# USB2UART.net
KiCad netlist of a schematic drawn in Altium Designer
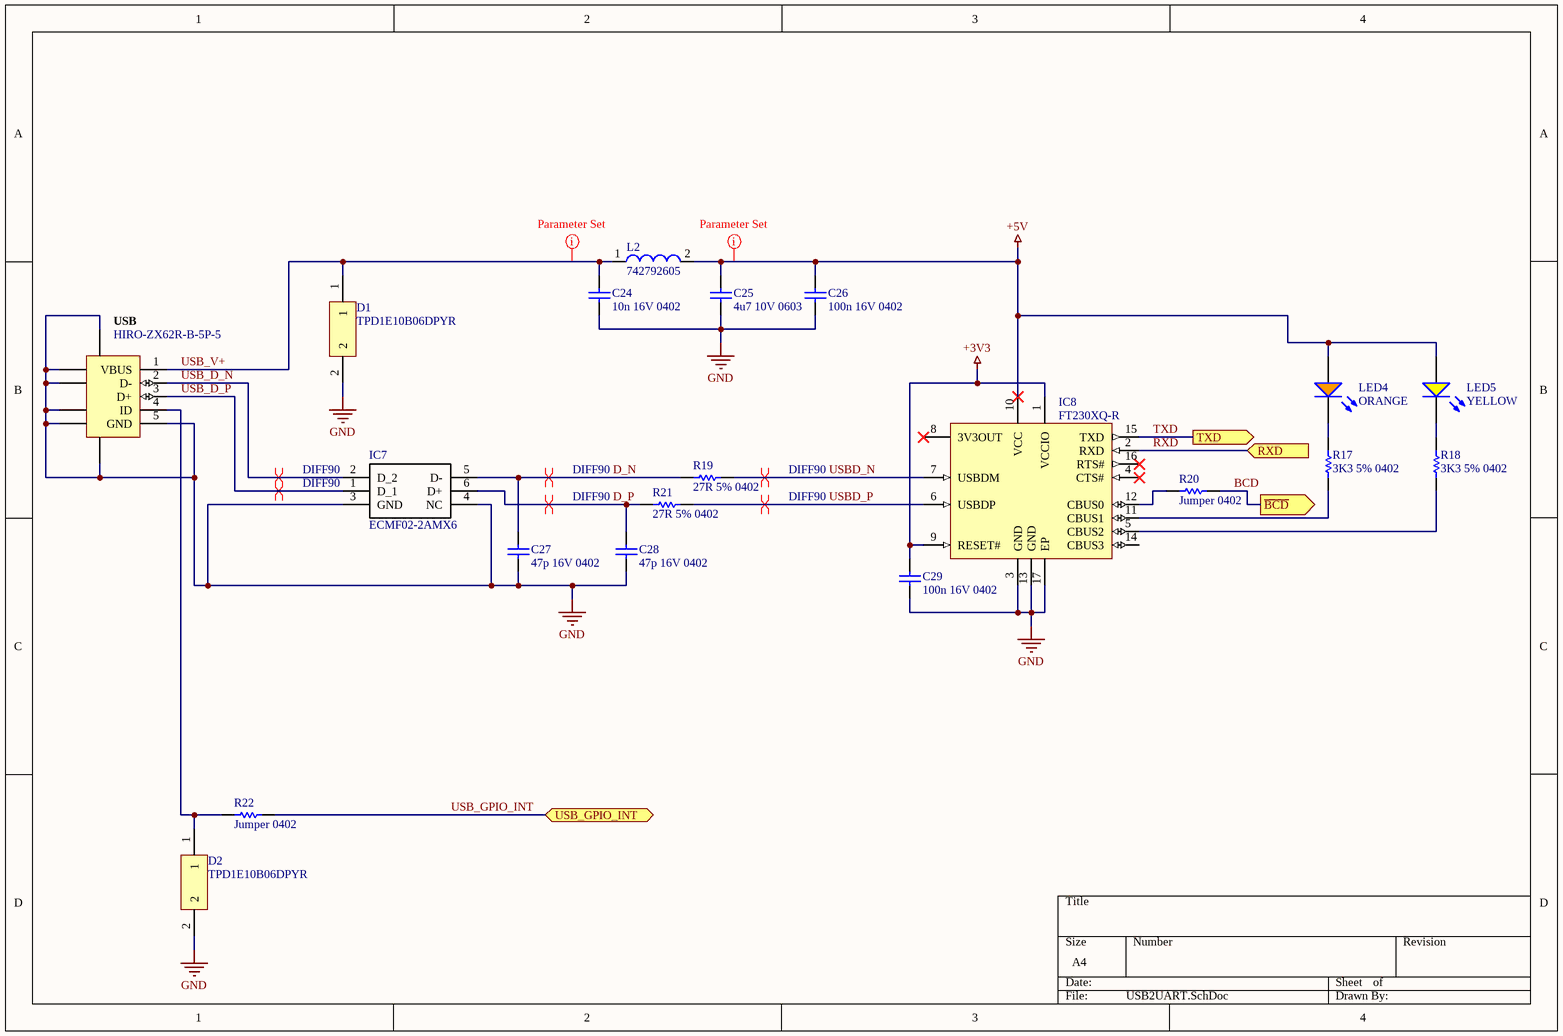
[diagram p0: USB2UART.SchDoc]

(export (version "E")
  (design (tool "Eeschema 10.0.6"))
  (components
    (comp (ref "C24")
      (value "10n 16V 0402")
      (footprint "CAPC0402(1005)33_L")
      (description "CAP 10nF 16V ±10% 0402 (1005 Metric) Thickness 0.33mm SMD")
      (fields (field (name "TOLERANCE") "Â±10%"))
      (libsource (lib "Altium Content Vault") (part "CAP"))
    )
    (comp (ref "C25")
      (value "4u7 10V 0603")
      (footprint "CAPC0603(1608)100_L")
      (description "CAP 4.7uF 10V ±20% 0603 (1608 Metric) Thickness 1mm SMD")
      (fields (field (name "TOLERANCE") "Â±20%"))
      (libsource (lib "Altium Content Vault") (part "CAP"))
    )
    (comp (ref "C26")
      (value "100n 16V 0402")
      (footprint "CAPC0402(1005)60_L")
      (description "CAP 100nF 16V ±10% 0402 (1005 Metric) Thickness 0.6mm SMD")
      (fields (field (name "TOLERANCE") "Â±10%"))
      (libsource (lib "Altium Content Vault") (part "CAP"))
    )
    (comp (ref "C27")
      (value "47p 16V 0402")
      (footprint "CAPC0402(1005)60_L")
      (description "CAP 47pF 16V ±10% 0402 (1005 Metric) Thickness 0.6mm SMD")
      (fields (field (name "TOLERANCE") "Â±10%"))
      (libsource (lib "Altium Content Vault") (part "CAP"))
    )
    (comp (ref "C28")
      (value "47p 16V 0402")
      (footprint "CAPC0402(1005)60_L")
      (description "CAP 47pF 16V ±10% 0402 (1005 Metric) Thickness 0.6mm SMD")
      (fields (field (name "TOLERANCE") "Â±10%"))
      (libsource (lib "Altium Content Vault") (part "CAP"))
    )
    (comp (ref "C29")
      (value "100n 16V 0402")
      (footprint "CAPC0402(1005)60_N")
      (description "CAP 100nF 16V ±10% 0402 (1005 Metric) Thickness 0.6mm SMD")
      (fields (field (name "TOLERANCE") "Â±10%"))
      (libsource (lib "Altium Content Vault") (part "CAP"))
    )
    (comp (ref "D1")
      (value "TPD1E10B06DPYR")
      (footprint "DPY0002A_M")
      (fields (field (name "MANUFACTURER") "Texas Instruments"))
      (libsource (lib "Altium Content Vault") (part "TI-TPD1E10B06-X2SON_DPY-2"))
    )
    (comp (ref "D2")
      (value "TPD1E10B06DPYR")
      (footprint "DPY0002A_M")
      (fields (field (name "MANUFACTURER") "Texas Instruments"))
      (libsource (lib "Altium Content Vault") (part "TI-TPD1E10B06-X2SON_DPY-2"))
    )
    (comp (ref "IC7")
      (value "ECMF02-2AMX6")
      (footprint "SON50P150X170X55-6N-D")
      (description "Integrated Circuit")
      (fields
        (field (name "MOUSER PART NUMBER") "511-ECMF02-2AMX6")
        (field (name "RS PART NUMBER") "8805276")
      )
      (libsource (lib "bleimuv6_intlib") (part "ECMF02-2AMX6"))
    )
    (comp (ref "IC8")
      (value "FT230XQ-R")
      (footprint "QFN-16_L")
      (fields (field (name "MANUFACTURER") "FTDI"))
      (libsource (lib "Altium Content Vault") (part "COM-USB-FT230XQ-SQ17"))
    )
    (comp (ref "L2")
      (value "742792605")
      (footprint "0603(1608)_L")
      (description "SMD EMI Suppression Ferrite Bead WE-CBF, Z = 33 Ohm")
      (libsource (lib "bleimuv6_intlib") (part "CMP-0220-00044-1"))
    )
    (comp (ref "LED4")
      (value "ORANGE")
      (footprint "LED_0402")
      (description "Generic 0402 LED")
      (libsource (lib "bleimuv6_schlib") (part "LED"))
    )
    (comp (ref "LED5")
      (value "YELLOW")
      (footprint "LED_0402")
      (description "Generic 0402 LED")
      (libsource (lib "bleimuv6_schlib") (part "LED"))
    )
    (comp (ref "R17")
      (value "3K3 5% 0402")
      (footprint "RESC0402(1005)_L")
      (description "3K3 0.063W 5% 0402 (1005 Metric)  SMD")
      (fields (field (name "POWER") "0.063 W") (field (name "TOLERANCE") "5 %"))
      (libsource (lib "Altium Content Vault") (part "RES"))
    )
    (comp (ref "R18")
      (value "3K3 5% 0402")
      (footprint "RESC0402(1005)_L")
      (description "3K3 0.063W 5% 0402 (1005 Metric)  SMD")
      (fields (field (name "POWER") "0.063 W") (field (name "TOLERANCE") "5 %"))
      (libsource (lib "Altium Content Vault") (part "RES"))
    )
    (comp (ref "R19")
      (value "27R 5% 0402")
      (footprint "RESC0402(1005)_L")
      (description "27R 0.063W 5% 0402 (1005 Metric)  SMD")
      (fields (field (name "TOLERANCE") "5 %") (field (name "POWER") "0.063 W"))
      (libsource (lib "Altium Content Vault") (part "RES"))
    )
    (comp (ref "R20")
      (value "Jumper 0402")
      (footprint "RESC0402(1005)_L")
      (description "Jumper 0402 (1005 Metric)")
      (fields (field (name "TOLERANCE") "None"))
      (libsource (lib "Altium Content Vault") (part "RES"))
    )
    (comp (ref "R21")
      (value "27R 5% 0402")
      (footprint "RESC0402(1005)_L")
      (description "27R 0.063W 5% 0402 (1005 Metric)  SMD")
      (fields (field (name "TOLERANCE") "5 %") (field (name "POWER") "0.063 W"))
      (libsource (lib "Altium Content Vault") (part "RES"))
    )
    (comp (ref "R22")
      (value "Jumper 0402")
      (footprint "RESC0402(1005)_L")
      (description "Jumper 0402 (1005 Metric)")
      (fields (field (name "TOLERANCE") "None"))
      (libsource (lib "Altium Content Vault") (part "RES"))
    )
    (comp (ref "USB")
      (value "HIRO-ZX62R-B-5P-5")
      (footprint "HIRO-ZX62R-B-5P_V")
      (libsource (lib "bleimuv6_intlib") (part "HIRO-ZX62R-B-5P-5"))
    )
  )
  (nets
    (net (code "1") (name "+3V3") (class "Default")
      (node (ref "C29") (pin "2") (pinfunction "2_2") (pintype "passive"))
      (node (ref "IC8") (pin "1") (pinfunction "VCCIO_1") (pintype "power_in"))
      (node (ref "IC8") (pin "9") (pinfunction "RESET#_9") (pintype "input"))
    )
    (net (code "2") (name "+5V") (class "Default")
      (node (ref "C25") (pin "2") (pinfunction "2_2") (pintype "passive"))
      (node (ref "C26") (pin "2") (pinfunction "2_2") (pintype "passive"))
      (node (ref "IC8") (pin "10") (pinfunction "VCC_10") (pintype "power_in"))
      (node (ref "L2") (pin "2") (pinfunction "2_2") (pintype "passive"))
      (node (ref "LED4") (pin "ANODE") (pinfunction "ANODE_ANODE") (pintype "passive"))
      (node (ref "LED5") (pin "ANODE") (pinfunction "ANODE_ANODE") (pintype "passive"))
    )
    (net (code "3") (name "/BCD") (class "Default")
      (node (ref "R20") (pin "2") (pinfunction "2_2") (pintype "passive"))
    )
    (net (code "4") (name "/D_N") (class "Default")
      (node (ref "C27") (pin "2") (pinfunction "2_2") (pintype "passive"))
      (node (ref "IC7") (pin "5") (pinfunction "D-_5") (pintype "passive"))
      (node (ref "R19") (pin "1") (pinfunction "1_1") (pintype "passive"))
    )
    (net (code "5") (name "/D_P") (class "Default")
      (node (ref "C28") (pin "2") (pinfunction "2_2") (pintype "passive"))
      (node (ref "IC7") (pin "6") (pinfunction "D+_6") (pintype "passive"))
      (node (ref "R21") (pin "1") (pinfunction "1_1") (pintype "passive"))
    )
    (net (code "6") (name "/RXD") (class "Default")
      (node (ref "IC8") (pin "2") (pinfunction "RXD_2") (pintype "input"))
    )
    (net (code "7") (name "/TXD") (class "Default")
      (node (ref "IC8") (pin "15") (pinfunction "TXD_15") (pintype "output"))
    )
    (net (code "8") (name "/USBD_N") (class "Default")
      (node (ref "IC8") (pin "7") (pinfunction "USBDM_7") (pintype "input"))
      (node (ref "R19") (pin "2") (pinfunction "2_2") (pintype "passive"))
    )
    (net (code "9") (name "/USBD_P") (class "Default")
      (node (ref "IC8") (pin "6") (pinfunction "USBDP_6") (pintype "input"))
      (node (ref "R21") (pin "2") (pinfunction "2_2") (pintype "passive"))
    )
    (net (code "10") (name "/USB_D_N") (class "Default")
      (node (ref "IC7") (pin "2") (pinfunction "D_2_2") (pintype "passive"))
      (node (ref "USB") (pin "2") (pinfunction "D-_2") (pintype "bidirectional"))
    )
    (net (code "11") (name "/USB_D_P") (class "Default")
      (node (ref "IC7") (pin "1") (pinfunction "D_1_1") (pintype "passive"))
      (node (ref "USB") (pin "3") (pinfunction "D+_3") (pintype "bidirectional"))
    )
    (net (code "12") (name "/USB_GPIO_INT") (class "Default")
      (node (ref "R22") (pin "2") (pinfunction "2_2") (pintype "passive"))
    )
    (net (code "13") (name "/USB_V+") (class "Default")
      (node (ref "C24") (pin "2") (pinfunction "2_2") (pintype "passive"))
      (node (ref "D1") (pin "1") (pinfunction "1_1") (pintype "passive"))
      (node (ref "L2") (pin "1") (pinfunction "1_1") (pintype "passive"))
      (node (ref "USB") (pin "1") (pinfunction "VBUS_1") (pintype "power_in"))
    )
    (net (code "14") (name "GND") (class "Default")
      (node (ref "C24") (pin "1") (pinfunction "1_1") (pintype "passive"))
      (node (ref "C25") (pin "1") (pinfunction "1_1") (pintype "passive"))
      (node (ref "C26") (pin "1") (pinfunction "1_1") (pintype "passive"))
      (node (ref "C27") (pin "1") (pinfunction "1_1") (pintype "passive"))
      (node (ref "C28") (pin "1") (pinfunction "1_1") (pintype "passive"))
      (node (ref "C29") (pin "1") (pinfunction "1_1") (pintype "passive"))
      (node (ref "D1") (pin "2") (pinfunction "2_2") (pintype "passive"))
      (node (ref "D2") (pin "2") (pinfunction "2_2") (pintype "passive"))
      (node (ref "IC7") (pin "3") (pinfunction "GND_3") (pintype "passive"))
      (node (ref "IC7") (pin "4") (pinfunction "NC_4") (pintype "passive"))
      (node (ref "IC8") (pin "13") (pinfunction "GND_13") (pintype "power_in"))
      (node (ref "IC8") (pin "17") (pinfunction "EP_17") (pintype "power_in"))
      (node (ref "IC8") (pin "3") (pinfunction "GND_3") (pintype "power_in"))
      (node (ref "USB") (pin "10") (pinfunction "SHLD_10") (pintype "passive"))
      (node (ref "USB") (pin "11") (pinfunction "SHLD_11") (pintype "passive"))
      (node (ref "USB") (pin "5") (pinfunction "GND_5") (pintype "power_in"))
      (node (ref "USB") (pin "6") (pinfunction "SHLD_6") (pintype "passive"))
      (node (ref "USB") (pin "7") (pinfunction "SHLD_7") (pintype "passive"))
      (node (ref "USB") (pin "8") (pinfunction "SHLD_8") (pintype "passive"))
      (node (ref "USB") (pin "9") (pinfunction "SHLD_9") (pintype "passive"))
    )
    (net (code "15") (name "Net-(IC8-CBUS0)") (class "Default")
      (node (ref "IC8") (pin "12") (pinfunction "CBUS0_12") (pintype "bidirectional"))
      (node (ref "R20") (pin "1") (pinfunction "1_1") (pintype "passive"))
    )
    (net (code "16") (name "Net-(IC8-CBUS1)") (class "Default")
      (node (ref "IC8") (pin "11") (pinfunction "CBUS1_11") (pintype "bidirectional"))
      (node (ref "R17") (pin "1") (pinfunction "1_1") (pintype "passive"))
    )
    (net (code "17") (name "Net-(IC8-CBUS2)") (class "Default")
      (node (ref "IC8") (pin "5") (pinfunction "CBUS2_5") (pintype "bidirectional"))
      (node (ref "R18") (pin "1") (pinfunction "1_1") (pintype "passive"))
    )
    (net (code "18") (name "Net-(LED4-PadCATHODE)") (class "Default")
      (node (ref "LED4") (pin "CATHODE") (pinfunction "CATHODE_CATHODE") (pintype "passive"))
      (node (ref "R17") (pin "2") (pinfunction "2_2") (pintype "passive"))
    )
    (net (code "19") (name "Net-(LED5-PadCATHODE)") (class "Default")
      (node (ref "LED5") (pin "CATHODE") (pinfunction "CATHODE_CATHODE") (pintype "passive"))
      (node (ref "R18") (pin "2") (pinfunction "2_2") (pintype "passive"))
    )
    (net (code "20") (name "Net-(USB-ID)") (class "Default")
      (node (ref "D2") (pin "1") (pinfunction "1_1") (pintype "passive"))
      (node (ref "R22") (pin "1") (pinfunction "1_1") (pintype "passive"))
      (node (ref "USB") (pin "4") (pinfunction "ID_4") (pintype "passive"))
    )
    (net (code "21") (name "unconnected-(IC8-3V3OUT-Pad8)") (class "Default")
      (node (ref "IC8") (pin "8") (pinfunction "3V3OUT_8") (pintype "power_in+no_connect"))
    )
    (net (code "22") (name "unconnected-(IC8-CBUS3-Pad14)") (class "Default")
      (node (ref "IC8") (pin "14") (pinfunction "CBUS3_14") (pintype "bidirectional"))
    )
    (net (code "23") (name "unconnected-(IC8-CTS#-Pad4)") (class "Default")
      (node (ref "IC8") (pin "4") (pinfunction "CTS#_4") (pintype "input+no_connect"))
    )
    (net (code "24") (name "unconnected-(IC8-RTS#-Pad16)") (class "Default")
      (node (ref "IC8") (pin "16") (pinfunction "RTS#_16") (pintype "output+no_connect"))
    )
  )
)
